# cc2650_rev2-1.net
KiCad netlist of a schematic drawn in EAGLE
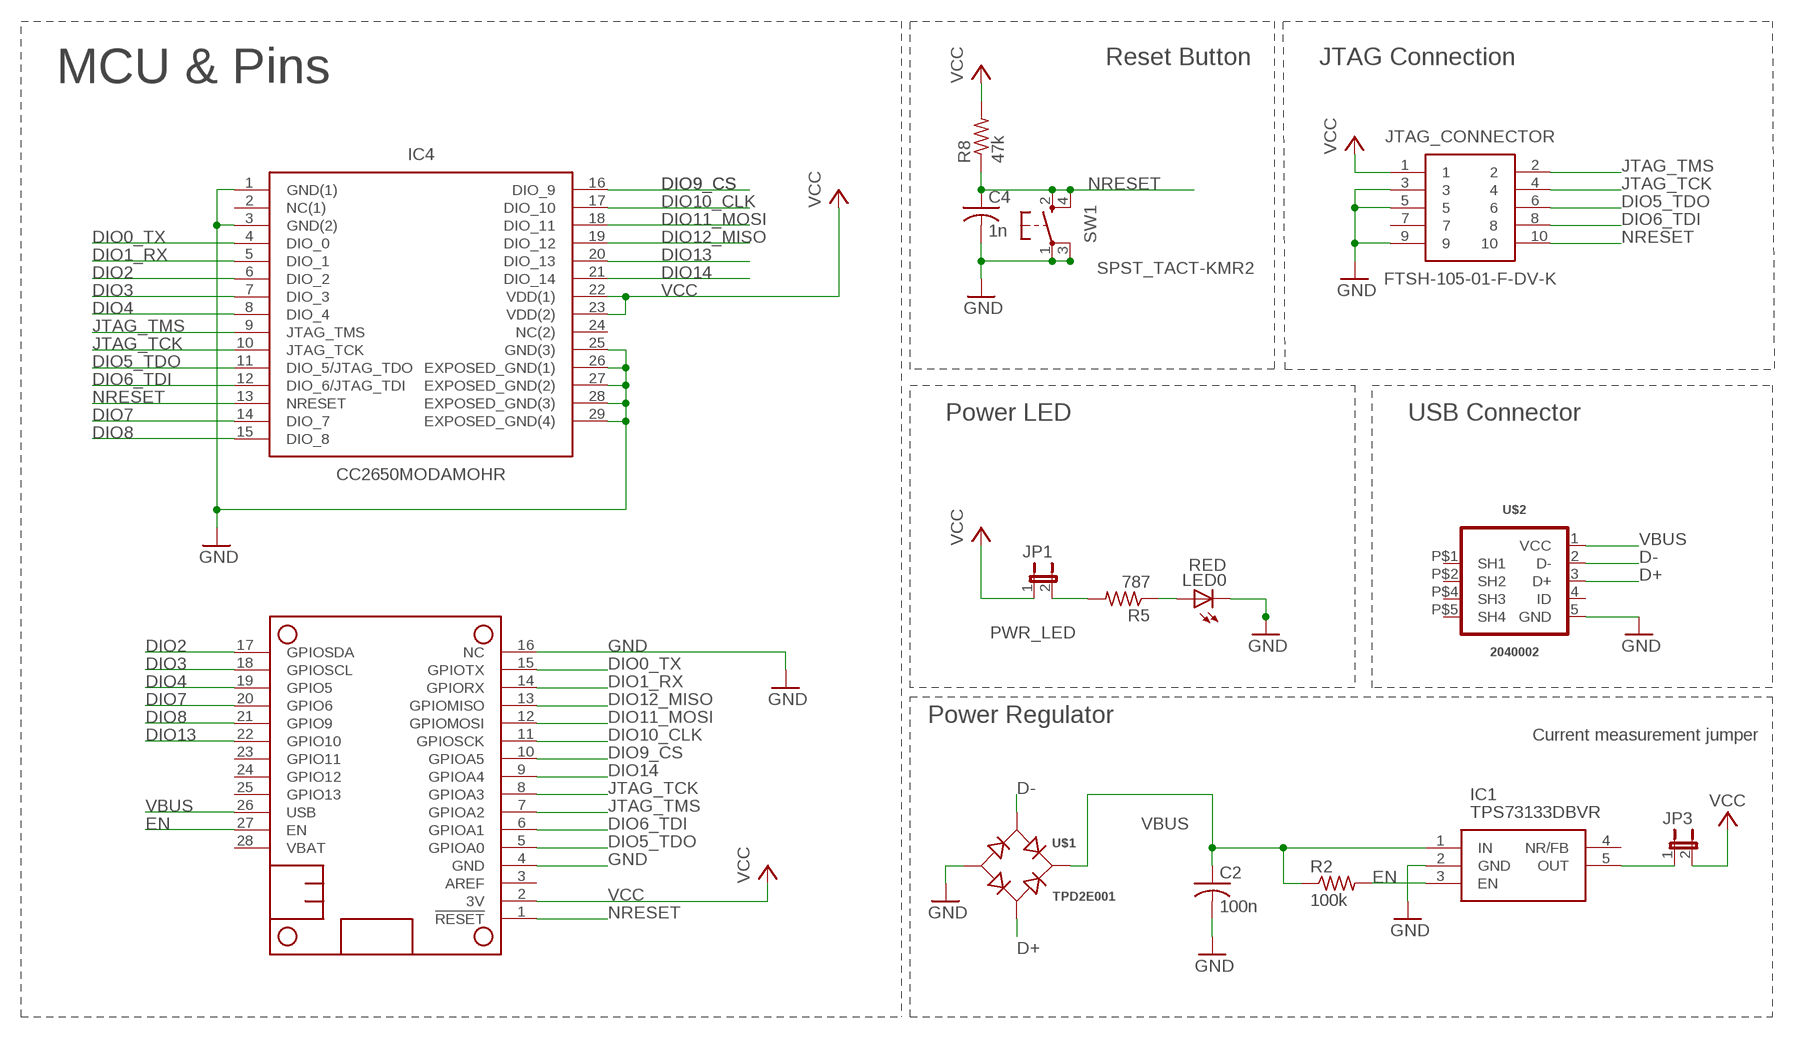
[diagram p0: schematic, sheet 1]
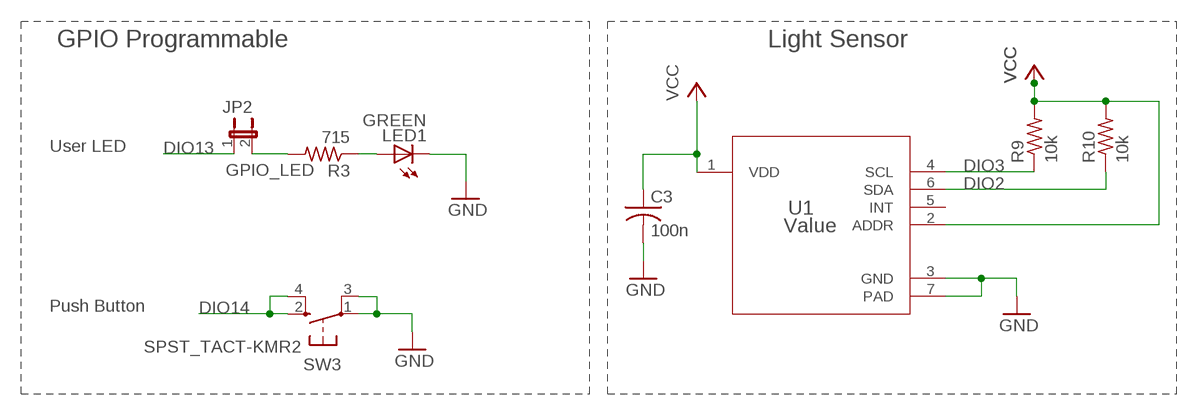
[diagram p1: schematic, sheet 2]

(export (version "E")
  (design (tool "Eeschema 10.0.6"))
  (components
    (comp (ref "C2")
      (value "100n")
      (footprint "eagle-import:C1206")
      (libsource (lib "eagle-import") (part "C-USC1206"))
    )
    (comp (ref "C4")
      (value "1n")
      (footprint "eagle-import:C1206")
      (libsource (lib "eagle-import") (part "C-USC1206"))
    )
    (comp (ref "IC1")
      (value "TPS73133DBVR")
      (footprint "eagle-import:SOT95P280X145-5N")
      (fields (field (name "RS_PART_NUMBER") "6613970"))
      (libsource (lib "eagle-import") (part "TPS73133DBVR"))
    )
    (comp (ref "IC4")
      (value "CC2650MODAMOHR")
      (footprint "eagle-import:MOH0029A")
      (libsource (lib "eagle-import") (part "CC2650MODAMOHR"))
    )
    (comp (ref "JP1")
      (value "PWR_LED")
      (footprint "eagle-import:JP1M")
      (fields (field (name "MPN") "2211S-02G"))
      (libsource (lib "eagle-import") (part "JP1M"))
    )
    (comp (ref "JP3")
      (value "PWR_LED")
      (footprint "eagle-import:JP1M")
      (fields (field (name "MPN") "2211S-02G"))
      (libsource (lib "eagle-import") (part "JP1M"))
    )
    (comp (ref "JTAG_CONNECTOR")
      (value "FTSH-105-01-F-DV-K")
      (footprint "eagle-import:SAMTEC_FTSH-105-01-L-DV")
      (libsource (lib "eagle-import") (part "FTSH-105-01-F-DV-K"))
    )
    (comp (ref "LED0")
      (value "RED")
      (footprint "eagle-import:CHIPLED_0603")
      (libsource (lib "eagle-import") (part "LEDCHIPLED_0603"))
    )
    (comp (ref "MS1")
      (value "FEATHERWING_NODIM")
      (footprint "eagle-import:FEATHERWING_DIM")
      (libsource (lib "eagle-import") (part "FEATHERWING_NODIM"))
    )
    (comp (ref "R2")
      (value "100k")
      (footprint "eagle-import:R1206")
      (libsource (lib "eagle-import") (part "R-US_R1206"))
    )
    (comp (ref "R5")
      (value "787")
      (footprint "eagle-import:R0603")
      (fields (field (name "MPN") "RC0603JR-07100KL"))
      (libsource (lib "eagle-import") (part "R-US_R0603"))
    )
    (comp (ref "R8")
      (value "47k")
      (footprint "eagle-import:R1206")
      (libsource (lib "eagle-import") (part "R-US_R1206"))
    )
    (comp (ref "SW1")
      (value "SPST_TACT-KMR2")
      (footprint "eagle-import:KMR2")
      (fields (field (name "MPN") "KMR241G LFS"))
      (libsource (lib "eagle-import") (part "SPST_TACT-KMR2"))
    )
    (comp (ref "U$1")
      (value "TPD2E001")
      (footprint "eagle-import:SOT-143")
      (libsource (lib "eagle-import") (part "TPD2E001"))
    )
    (comp (ref "U$2")
      (value "2040002")
      (footprint "eagle-import:2040002")
      (libsource (lib "eagle-import") (part "2040002"))
    )
    (comp (ref "C3")
      (value "100n")
      (footprint "eagle-import:C1206")
      (libsource (lib "eagle-import") (part "C-USC1206"))
    )
    (comp (ref "JP2")
      (value "GPIO_LED")
      (footprint "eagle-import:JP1M")
      (fields (field (name "MPN") "2211S-02G"))
      (libsource (lib "eagle-import") (part "JP1M"))
    )
    (comp (ref "LED1")
      (value "GREEN")
      (footprint "eagle-import:CHIPLED_0603")
      (libsource (lib "eagle-import") (part "LEDCHIPLED_0603"))
    )
    (comp (ref "R3")
      (value "715")
      (footprint "eagle-import:R0603")
      (fields (field (name "MPN") "RC0603JR-07100KL"))
      (libsource (lib "eagle-import") (part "R-US_R0603"))
    )
    (comp (ref "R9")
      (value "10k")
      (footprint "eagle-import:R1206")
      (libsource (lib "eagle-import") (part "R-US_R1206"))
    )
    (comp (ref "R10")
      (value "10k")
      (footprint "eagle-import:R1206")
      (libsource (lib "eagle-import") (part "R-US_R1206"))
    )
    (comp (ref "SW3")
      (value "SPST_TACT-KMR2")
      (footprint "eagle-import:KMR2")
      (fields (field (name "MPN") "KMR241G LFS"))
      (libsource (lib "eagle-import") (part "SPST_TACT-KMR2"))
    )
    (comp (ref "U1")
      (value "Value")
      (footprint "eagle-import:DNP0006A")
      (fields (field (name "MANUFACTURER") "Texas Instruments") (field (name "PARTNUMBER") "OPT3001DNP"))
      (libsource (lib "eagle-import") (part "OPT3001DNPR"))
    )
  )
  (nets
    (net (code "1") (name "D+") (class "Default")
      (node (ref "U$1") (pin "3") (pinfunction "AC2_3") (pintype "passive"))
      (node (ref "U$2") (pin "3") (pinfunction "D+_3") (pintype "bidirectional"))
    )
    (net (code "2") (name "D-") (class "Default")
      (node (ref "U$1") (pin "2") (pinfunction "AC1_2") (pintype "passive"))
      (node (ref "U$2") (pin "2") (pinfunction "D-_2") (pintype "bidirectional"))
    )
    (net (code "3") (name "DIO0_TX") (class "Default")
      (node (ref "IC4") (pin "4") (pinfunction "DIO_0_4") (pintype "passive"))
      (node (ref "MS1") (pin "15") (pinfunction "GPIOTX_15") (pintype "bidirectional"))
    )
    (net (code "4") (name "DIO1_RX") (class "Default")
      (node (ref "IC4") (pin "5") (pinfunction "DIO_1_5") (pintype "passive"))
      (node (ref "MS1") (pin "14") (pinfunction "GPIORX_14") (pintype "bidirectional"))
    )
    (net (code "5") (name "DIO2") (class "Default")
      (node (ref "IC4") (pin "6") (pinfunction "DIO_2_6") (pintype "passive"))
      (node (ref "MS1") (pin "17") (pinfunction "GPIOSDA_17") (pintype "bidirectional"))
      (node (ref "R10") (pin "1") (pinfunction "1_1") (pintype "passive"))
      (node (ref "U1") (pin "6") (pinfunction "SDA_6") (pintype "input"))
    )
    (net (code "6") (name "DIO3") (class "Default")
      (node (ref "IC4") (pin "7") (pinfunction "DIO_3_7") (pintype "passive"))
      (node (ref "MS1") (pin "18") (pinfunction "GPIOSCL_18") (pintype "bidirectional"))
      (node (ref "R9") (pin "1") (pinfunction "1_1") (pintype "passive"))
      (node (ref "U1") (pin "4") (pinfunction "SCL_4") (pintype "input"))
    )
    (net (code "7") (name "DIO4") (class "Default")
      (node (ref "IC4") (pin "8") (pinfunction "DIO_4_8") (pintype "passive"))
      (node (ref "MS1") (pin "19") (pinfunction "GPIO5_19") (pintype "bidirectional"))
    )
    (net (code "8") (name "DIO5_TDO") (class "Default")
      (node (ref "IC4") (pin "11") (pinfunction "DIO_5/JTAG_TDO_11") (pintype "passive"))
      (node (ref "JTAG_CONNECTOR") (pin "6") (pinfunction "6_6") (pintype "passive"))
      (node (ref "MS1") (pin "5") (pinfunction "GPIOA0_5") (pintype "bidirectional"))
    )
    (net (code "9") (name "DIO6_TDI") (class "Default")
      (node (ref "IC4") (pin "12") (pinfunction "DIO_6/JTAG_TDI_12") (pintype "passive"))
      (node (ref "JTAG_CONNECTOR") (pin "8") (pinfunction "8_8") (pintype "passive"))
      (node (ref "MS1") (pin "6") (pinfunction "GPIOA1_6") (pintype "bidirectional"))
    )
    (net (code "10") (name "DIO7") (class "Default")
      (node (ref "IC4") (pin "14") (pinfunction "DIO_7_14") (pintype "passive"))
      (node (ref "MS1") (pin "20") (pinfunction "GPIO6_20") (pintype "bidirectional"))
    )
    (net (code "11") (name "DIO8") (class "Default")
      (node (ref "IC4") (pin "15") (pinfunction "DIO_8_15") (pintype "passive"))
      (node (ref "MS1") (pin "21") (pinfunction "GPIO9_21") (pintype "bidirectional"))
    )
    (net (code "12") (name "DIO9_CS") (class "Default")
      (node (ref "IC4") (pin "16") (pinfunction "DIO_9_16") (pintype "passive"))
      (node (ref "MS1") (pin "10") (pinfunction "GPIOA5_10") (pintype "bidirectional"))
    )
    (net (code "13") (name "DIO10_CLK") (class "Default")
      (node (ref "IC4") (pin "17") (pinfunction "DIO_10_17") (pintype "passive"))
      (node (ref "MS1") (pin "11") (pinfunction "GPIOSCK_11") (pintype "bidirectional"))
    )
    (net (code "14") (name "DIO11_MOSI") (class "Default")
      (node (ref "IC4") (pin "18") (pinfunction "DIO_11_18") (pintype "passive"))
      (node (ref "MS1") (pin "12") (pinfunction "GPIOMOSI_12") (pintype "bidirectional"))
    )
    (net (code "15") (name "DIO12_MISO") (class "Default")
      (node (ref "IC4") (pin "19") (pinfunction "DIO_12_19") (pintype "passive"))
      (node (ref "MS1") (pin "13") (pinfunction "GPIOMISO_13") (pintype "bidirectional"))
    )
    (net (code "16") (name "DIO13") (class "Default")
      (node (ref "IC4") (pin "20") (pinfunction "DIO_13_20") (pintype "passive"))
      (node (ref "JP2") (pin "1") (pinfunction "1_1") (pintype "passive"))
      (node (ref "MS1") (pin "22") (pinfunction "GPIO10_22") (pintype "bidirectional"))
    )
    (net (code "17") (name "DIO14") (class "Default")
      (node (ref "IC4") (pin "21") (pinfunction "DIO_14_21") (pintype "passive"))
      (node (ref "MS1") (pin "9") (pinfunction "GPIOA4_9") (pintype "bidirectional"))
      (node (ref "SW3") (pin "2") (pinfunction "S_2") (pintype "passive"))
      (node (ref "SW3") (pin "4") (pinfunction "S1_4") (pintype "passive"))
    )
    (net (code "18") (name "EN") (class "Default")
      (node (ref "IC1") (pin "3") (pinfunction "EN_3") (pintype "input"))
      (node (ref "MS1") (pin "27") (pinfunction "EN_27") (pintype "passive"))
      (node (ref "R2") (pin "2") (pinfunction "2_2") (pintype "passive"))
    )
    (net (code "19") (name "GND") (class "Default")
      (node (ref "C2") (pin "2") (pinfunction "2_2") (pintype "passive"))
      (node (ref "C3") (pin "2") (pinfunction "2_2") (pintype "passive"))
      (node (ref "C4") (pin "2") (pinfunction "2_2") (pintype "passive"))
      (node (ref "IC1") (pin "2") (pinfunction "GND_2") (pintype "input"))
      (node (ref "IC4") (pin "1") (pinfunction "GND(1)_1") (pintype "passive"))
      (node (ref "IC4") (pin "25") (pinfunction "GND(3)_25") (pintype "passive"))
      (node (ref "IC4") (pin "26") (pinfunction "EXPOSED_GND(1)_26") (pintype "passive"))
      (node (ref "IC4") (pin "27") (pinfunction "EXPOSED_GND(2)_27") (pintype "passive"))
      (node (ref "IC4") (pin "28") (pinfunction "EXPOSED_GND(3)_28") (pintype "passive"))
      (node (ref "IC4") (pin "29") (pinfunction "EXPOSED_GND(4)_29") (pintype "passive"))
      (node (ref "IC4") (pin "3") (pinfunction "GND(2)_3") (pintype "passive"))
      (node (ref "JTAG_CONNECTOR") (pin "3") (pinfunction "3_3") (pintype "passive"))
      (node (ref "JTAG_CONNECTOR") (pin "5") (pinfunction "5_5") (pintype "passive"))
      (node (ref "JTAG_CONNECTOR") (pin "9") (pinfunction "9_9") (pintype "passive"))
      (node (ref "LED0") (pin "C") (pinfunction "C_C") (pintype "passive"))
      (node (ref "LED1") (pin "C") (pinfunction "C_C") (pintype "passive"))
      (node (ref "MS1") (pin "16") (pinfunction "NC_16") (pintype "passive"))
      (node (ref "MS1") (pin "4") (pinfunction "GND_4") (pintype "power_in"))
      (node (ref "SW1") (pin "1") (pinfunction "P_1") (pintype "passive"))
      (node (ref "SW1") (pin "3") (pinfunction "P1_3") (pintype "passive"))
      (node (ref "SW3") (pin "1") (pinfunction "P_1") (pintype "passive"))
      (node (ref "SW3") (pin "3") (pinfunction "P1_3") (pintype "passive"))
      (node (ref "U$1") (pin "1") (pinfunction "-_1") (pintype "passive"))
      (node (ref "U$2") (pin "5") (pinfunction "GND_5") (pintype "bidirectional"))
      (node (ref "U1") (pin "3") (pinfunction "GND_3") (pintype "power_in"))
      (node (ref "U1") (pin "7") (pinfunction "PAD_7") (pintype "passive"))
    )
    (net (code "20") (name "JTAG_TCK") (class "Default")
      (node (ref "IC4") (pin "10") (pinfunction "JTAG_TCK_10") (pintype "passive"))
      (node (ref "JTAG_CONNECTOR") (pin "4") (pinfunction "4_4") (pintype "passive"))
      (node (ref "MS1") (pin "8") (pinfunction "GPIOA3_8") (pintype "bidirectional"))
    )
    (net (code "21") (name "JTAG_TMS") (class "Default")
      (node (ref "IC4") (pin "9") (pinfunction "JTAG_TMS_9") (pintype "passive"))
      (node (ref "JTAG_CONNECTOR") (pin "2") (pinfunction "2_2") (pintype "passive"))
      (node (ref "MS1") (pin "7") (pinfunction "GPIOA2_7") (pintype "bidirectional"))
    )
    (net (code "22") (name "NRESET") (class "Default")
      (node (ref "C4") (pin "1") (pinfunction "1_1") (pintype "passive"))
      (node (ref "IC4") (pin "13") (pinfunction "NRESET_13") (pintype "passive"))
      (node (ref "JTAG_CONNECTOR") (pin "10") (pinfunction "10_10") (pintype "passive"))
      (node (ref "MS1") (pin "1") (pinfunction "~{RESET}_1") (pintype "input"))
      (node (ref "R8") (pin "1") (pinfunction "1_1") (pintype "passive"))
      (node (ref "SW1") (pin "2") (pinfunction "S_2") (pintype "passive"))
      (node (ref "SW1") (pin "4") (pinfunction "S1_4") (pintype "passive"))
    )
    (net (code "23") (name "Net-(IC1-OUT)") (class "Default")
      (node (ref "IC1") (pin "5") (pinfunction "OUT_5") (pintype "input"))
      (node (ref "JP3") (pin "1") (pinfunction "1_1") (pintype "passive"))
    )
    (net (code "24") (name "Net-(JP1-Pad2)") (class "Default")
      (node (ref "JP1") (pin "2") (pinfunction "2_2") (pintype "passive"))
      (node (ref "R5") (pin "2") (pinfunction "2_2") (pintype "passive"))
    )
    (net (code "25") (name "Net-(JP2-Pad2)") (class "Default")
      (node (ref "JP2") (pin "2") (pinfunction "2_2") (pintype "passive"))
      (node (ref "R3") (pin "2") (pinfunction "2_2") (pintype "passive"))
    )
    (net (code "26") (name "Net-(LED0-PadA)") (class "Default")
      (node (ref "LED0") (pin "A") (pinfunction "A_A") (pintype "passive"))
      (node (ref "R5") (pin "1") (pinfunction "1_1") (pintype "passive"))
    )
    (net (code "27") (name "Net-(LED1-PadA)") (class "Default")
      (node (ref "LED1") (pin "A") (pinfunction "A_A") (pintype "passive"))
      (node (ref "R3") (pin "1") (pinfunction "1_1") (pintype "passive"))
    )
    (net (code "28") (name "VBAT") (class "Default")
      (node (ref "MS1") (pin "28") (pinfunction "VBAT_28") (pintype "power_in"))
    )
    (net (code "29") (name "VBUS") (class "Default")
      (node (ref "C2") (pin "1") (pinfunction "1_1") (pintype "passive"))
      (node (ref "IC1") (pin "1") (pinfunction "IN_1") (pintype "input"))
      (node (ref "MS1") (pin "26") (pinfunction "USB_26") (pintype "power_in"))
      (node (ref "R2") (pin "1") (pinfunction "1_1") (pintype "passive"))
      (node (ref "U$1") (pin "4") (pinfunction "+_4") (pintype "passive"))
      (node (ref "U$2") (pin "1") (pinfunction "VCC_1") (pintype "bidirectional"))
    )
    (net (code "30") (name "VCC") (class "Default")
      (node (ref "C3") (pin "1") (pinfunction "1_1") (pintype "passive"))
      (node (ref "IC4") (pin "22") (pinfunction "VDD(1)_22") (pintype "passive"))
      (node (ref "IC4") (pin "23") (pinfunction "VDD(2)_23") (pintype "passive"))
      (node (ref "JP1") (pin "1") (pinfunction "1_1") (pintype "passive"))
      (node (ref "JP3") (pin "2") (pinfunction "2_2") (pintype "passive"))
      (node (ref "JTAG_CONNECTOR") (pin "1") (pinfunction "1_1") (pintype "passive"))
      (node (ref "MS1") (pin "2") (pinfunction "3V_2") (pintype "power_in"))
      (node (ref "R10") (pin "2") (pinfunction "2_2") (pintype "passive"))
      (node (ref "R8") (pin "2") (pinfunction "2_2") (pintype "passive"))
      (node (ref "R9") (pin "2") (pinfunction "2_2") (pintype "passive"))
      (node (ref "U1") (pin "1") (pinfunction "VDD_1") (pintype "power_in"))
      (node (ref "U1") (pin "2") (pinfunction "ADDR_2") (pintype "input"))
    )
    (net (code "31") (name "unconnected-(IC1-NR{slash}FB-Pad4)") (class "Default")
      (node (ref "IC1") (pin "4") (pinfunction "NR/FB_4") (pintype "input"))
    )
    (net (code "32") (name "unconnected-(IC4-NC(1)-Pad2)") (class "Default")
      (node (ref "IC4") (pin "2") (pinfunction "NC(1)_2") (pintype "passive"))
    )
    (net (code "33") (name "unconnected-(IC4-NC(2)-Pad24)") (class "Default")
      (node (ref "IC4") (pin "24") (pinfunction "NC(2)_24") (pintype "passive"))
    )
    (net (code "34") (name "unconnected-(JTAG_CONNECTOR-Pad7)") (class "Default")
      (node (ref "JTAG_CONNECTOR") (pin "7") (pinfunction "7_7") (pintype "passive"))
    )
    (net (code "35") (name "unconnected-(MS1-AREF-Pad3)") (class "Default")
      (node (ref "MS1") (pin "3") (pinfunction "AREF_3") (pintype "passive"))
    )
    (net (code "36") (name "unconnected-(MS1-GPIO11-Pad23)") (class "Default")
      (node (ref "MS1") (pin "23") (pinfunction "GPIO11_23") (pintype "bidirectional"))
    )
    (net (code "37") (name "unconnected-(MS1-GPIO12-Pad24)") (class "Default")
      (node (ref "MS1") (pin "24") (pinfunction "GPIO12_24") (pintype "bidirectional"))
    )
    (net (code "38") (name "unconnected-(MS1-GPIO13-Pad25)") (class "Default")
      (node (ref "MS1") (pin "25") (pinfunction "GPIO13_25") (pintype "bidirectional"))
    )
    (net (code "39") (name "unconnected-(U$2-ID-Pad4)") (class "Default")
      (node (ref "U$2") (pin "4") (pinfunction "ID_4") (pintype "bidirectional"))
    )
    (net (code "40") (name "unconnected-(U$2-SH1-PadP$1)") (class "Default")
      (node (ref "U$2") (pin "P$1") (pinfunction "SH1_P$1") (pintype "no_connect"))
    )
    (net (code "41") (name "unconnected-(U$2-SH2-PadP$2)") (class "Default")
      (node (ref "U$2") (pin "P$2") (pinfunction "SH2_P$2") (pintype "no_connect"))
    )
    (net (code "42") (name "unconnected-(U$2-SH3-PadP$4)") (class "Default")
      (node (ref "U$2") (pin "P$4") (pinfunction "SH3_P$4") (pintype "no_connect"))
    )
    (net (code "43") (name "unconnected-(U$2-SH4-PadP$5)") (class "Default")
      (node (ref "U$2") (pin "P$5") (pinfunction "SH4_P$5") (pintype "no_connect"))
    )
    (net (code "44") (name "unconnected-(U1-INT-Pad5)") (class "Default")
      (node (ref "U1") (pin "5") (pinfunction "INT_5") (pintype "output"))
    )
  )
)
